# 611_jetbot_129.net
KiCad netlist of a schematic drawn in EAGLE
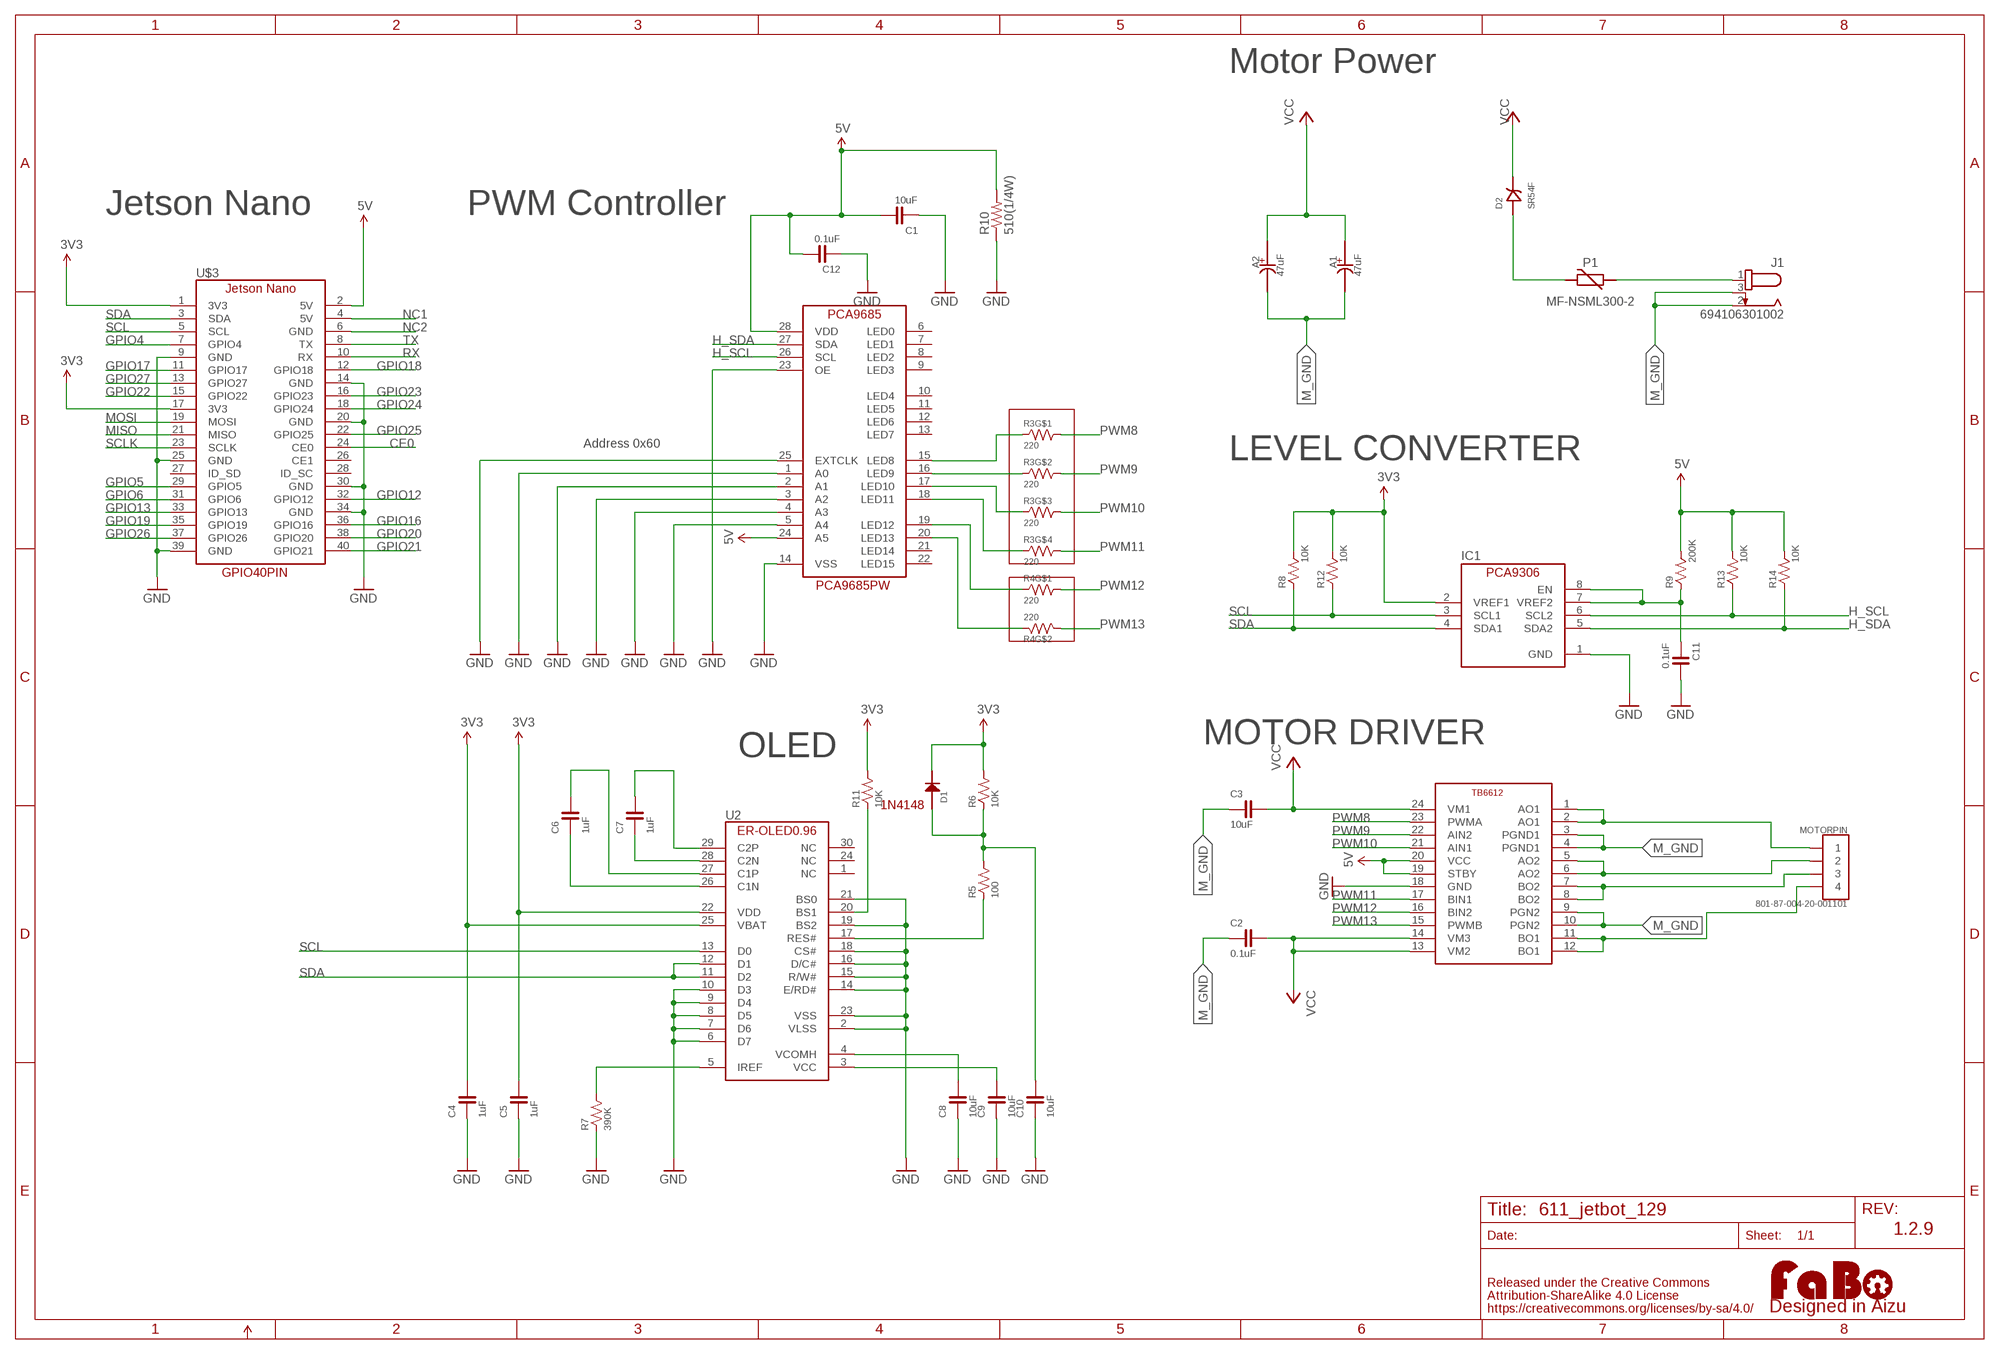
[diagram p0: schematic, sheet 1]

(export (version "E")
  (design (tool "Eeschema 10.0.6"))
  (components
    (comp (ref "A1")
      (value "47uF")
      (footprint "eagle-import:D60")
      (libsource (lib "eagle-import") (part "CAPACITOR-ALUMIN_D60"))
    )
    (comp (ref "A2")
      (value "47uF")
      (footprint "eagle-import:D60")
      (libsource (lib "eagle-import") (part "CAPACITOR-ALUMIN_D60"))
    )
    (comp (ref "C1")
      (value "10uF")
      (footprint "eagle-import:0603")
      (libsource (lib "eagle-import") (part "CAPACITOR-0603"))
    )
    (comp (ref "C2")
      (value "0.1uF")
      (footprint "eagle-import:0603")
      (libsource (lib "eagle-import") (part "CAPACITOR-0603"))
    )
    (comp (ref "C3")
      (value "10uF")
      (footprint "eagle-import:0603")
      (libsource (lib "eagle-import") (part "CAPACITOR-0603"))
    )
    (comp (ref "C4")
      (value "1uF")
      (footprint "eagle-import:0603-BOTTOM")
      (libsource (lib "eagle-import") (part "CAPACITOR-0603-BOTTOM"))
    )
    (comp (ref "C5")
      (value "1uF")
      (footprint "eagle-import:0603-BOTTOM")
      (libsource (lib "eagle-import") (part "CAPACITOR-0603-BOTTOM"))
    )
    (comp (ref "C6")
      (value "1uF")
      (footprint "eagle-import:0603-BOTTOM")
      (libsource (lib "eagle-import") (part "CAPACITOR-0603-BOTTOM"))
    )
    (comp (ref "C7")
      (value "1uF")
      (footprint "eagle-import:0603-BOTTOM")
      (libsource (lib "eagle-import") (part "CAPACITOR-0603-BOTTOM"))
    )
    (comp (ref "C8")
      (value "10uF")
      (footprint "eagle-import:0603-BOTTOM")
      (libsource (lib "eagle-import") (part "CAPACITOR-0603-BOTTOM"))
    )
    (comp (ref "C9")
      (value "10uF")
      (footprint "eagle-import:0603-BOTTOM")
      (libsource (lib "eagle-import") (part "CAPACITOR-0603-BOTTOM"))
    )
    (comp (ref "C10")
      (value "10uF")
      (footprint "eagle-import:0603-BOTTOM")
      (libsource (lib "eagle-import") (part "CAPACITOR-0603-BOTTOM"))
    )
    (comp (ref "C11")
      (value "0.1uF")
      (footprint "eagle-import:0603")
      (libsource (lib "eagle-import") (part "CAPACITOR-0603"))
    )
    (comp (ref "C12")
      (value "0.1uF")
      (footprint "eagle-import:0603")
      (libsource (lib "eagle-import") (part "CAPACITOR-0603"))
    )
    (comp (ref "D1")
      (value "1N4148")
      (footprint "eagle-import:1N4148W")
      (libsource (lib "eagle-import") (part "1N4148"))
    )
    (comp (ref "D2")
      (value "SR54F")
      (footprint "eagle-import:SMBF")
      (libsource (lib "eagle-import") (part "SR54F"))
    )
    (comp (ref "IC1")
      (value "PCA9306_SSOP")
      (footprint "eagle-import:8PIN-SSOP")
      (libsource (lib "eagle-import") (part "PCA9306_SSOP"))
    )
    (comp (ref "IC4")
      (value "PCA9685")
      (footprint "eagle-import:PCA9685")
      (libsource (lib "eagle-import") (part "PCA9685"))
    )
    (comp (ref "J1")
      (value "694106301002")
      (footprint "eagle-import:694106301002")
      (fields
        (field (name "DIGIKEY_PART_NUMBER") "732-5930-ND")
        (field (name "MANUFACTURER") "Wurth Electronics Inc.")
        (field (name "CREATED_BY") "PCBLayout.com")
      )
      (libsource (lib "eagle-import") (part "694106301002"))
    )
    (comp (ref "LOGO1")
      (value "LOGO_FABO-M")
      (footprint "eagle-import:LOGO_FABO_M")
      (libsource (lib "eagle-import") (part "LOGO_FABO-M"))
    )
    (comp (ref "MOTORPIN")
      (value "801-87-004-20-001101")
      (footprint "eagle-import:801-87-004-20-002101")
      (libsource (lib "eagle-import") (part "801-87-004-20-001101"))
    )
    (comp (ref "P1")
      (value "MF-NSML300-2")
      (footprint "eagle-import:1206")
      (libsource (lib "eagle-import") (part "POLYSWITCH1206"))
    )
    (comp (ref "R3")
      (value "220")
      (footprint "eagle-import:EXBV8V")
      (libsource (lib "eagle-import") (part "RESISTOR_ARRAY"))
    )
    (comp (ref "R4")
      (value "220")
      (footprint "eagle-import:EXBV8V")
      (libsource (lib "eagle-import") (part "RESISTOR_ARRAY"))
    )
    (comp (ref "R5")
      (value "100")
      (footprint "eagle-import:0603-BOTTOM")
      (libsource (lib "eagle-import") (part "RESISTOR-0603-BOTTOM"))
    )
    (comp (ref "R6")
      (value "10K")
      (footprint "eagle-import:0603-BOTTOM")
      (libsource (lib "eagle-import") (part "RESISTOR-0603-BOTTOM"))
    )
    (comp (ref "R7")
      (value "390K")
      (footprint "eagle-import:0603-BOTTOM")
      (libsource (lib "eagle-import") (part "RESISTOR-0603-BOTTOM"))
    )
    (comp (ref "R8")
      (value "10K")
      (footprint "eagle-import:0603")
      (libsource (lib "eagle-import") (part "RESISTOR-0603"))
    )
    (comp (ref "R9")
      (value "200K")
      (footprint "eagle-import:0603")
      (libsource (lib "eagle-import") (part "RESISTOR-0603"))
    )
    (comp (ref "R10")
      (value "510(1/4W)")
      (footprint "eagle-import:R0805")
      (libsource (lib "eagle-import") (part "R-US_R0805"))
    )
    (comp (ref "R11")
      (value "10K")
      (footprint "eagle-import:0603-BOTTOM")
      (libsource (lib "eagle-import") (part "RESISTOR-0603-BOTTOM"))
    )
    (comp (ref "R12")
      (value "10K")
      (footprint "eagle-import:0603")
      (libsource (lib "eagle-import") (part "RESISTOR-0603"))
    )
    (comp (ref "R13")
      (value "10K")
      (footprint "eagle-import:0603")
      (libsource (lib "eagle-import") (part "RESISTOR-0603"))
    )
    (comp (ref "R14")
      (value "10K")
      (footprint "eagle-import:0603")
      (libsource (lib "eagle-import") (part "RESISTOR-0603"))
    )
    (comp (ref "U$3")
      (value "JETSON_NANO")
      (footprint "eagle-import:JETSON_NANO")
      (libsource (lib "eagle-import") (part "JETSON_NANO"))
    )
    (comp (ref "U$5")
      (value "TB6612")
      (footprint "eagle-import:TB6612")
      (libsource (lib "eagle-import") (part "TB6612"))
    )
    (comp (ref "U2")
      (value "ER-OLED0.96-1ER-CON30HT-1_REV2")
      (footprint "eagle-import:ER-CON30HT-1_REV2")
      (libsource (lib "eagle-import") (part "ER-OLED0.96-1ER-CON30HT-1_REV2"))
    )
  )
  (nets
    (net (code "1") (name "/CE0") (class "Default")
      (node (ref "U$3") (pin "24") (pinfunction "CE0_24") (pintype "bidirectional"))
    )
    (net (code "2") (name "/GPIO4") (class "Default")
      (node (ref "U$3") (pin "7") (pinfunction "GPIO4_7") (pintype "bidirectional"))
    )
    (net (code "3") (name "/GPIO5") (class "Default")
      (node (ref "U$3") (pin "29") (pinfunction "GPIO5_29") (pintype "bidirectional"))
    )
    (net (code "4") (name "/GPIO6") (class "Default")
      (node (ref "U$3") (pin "31") (pinfunction "GPIO6_31") (pintype "bidirectional"))
    )
    (net (code "5") (name "/GPIO12") (class "Default")
      (node (ref "U$3") (pin "32") (pinfunction "GPIO12_32") (pintype "bidirectional"))
    )
    (net (code "6") (name "/GPIO13") (class "Default")
      (node (ref "U$3") (pin "33") (pinfunction "GPIO13_33") (pintype "bidirectional"))
    )
    (net (code "7") (name "/GPIO16") (class "Default")
      (node (ref "U$3") (pin "36") (pinfunction "GPIO16_36") (pintype "bidirectional"))
    )
    (net (code "8") (name "/GPIO17") (class "Default")
      (node (ref "U$3") (pin "11") (pinfunction "GPIO17_11") (pintype "bidirectional"))
    )
    (net (code "9") (name "/GPIO18") (class "Default")
      (node (ref "U$3") (pin "12") (pinfunction "GPIO18_12") (pintype "bidirectional"))
    )
    (net (code "10") (name "/GPIO19") (class "Default")
      (node (ref "U$3") (pin "35") (pinfunction "GPIO19_35") (pintype "bidirectional"))
    )
    (net (code "11") (name "/GPIO20") (class "Default")
      (node (ref "U$3") (pin "38") (pinfunction "GPIO20_38") (pintype "bidirectional"))
    )
    (net (code "12") (name "/GPIO21") (class "Default")
      (node (ref "U$3") (pin "40") (pinfunction "GPIO21_40") (pintype "bidirectional"))
    )
    (net (code "13") (name "/GPIO22") (class "Default")
      (node (ref "U$3") (pin "15") (pinfunction "GPIO22_15") (pintype "bidirectional"))
    )
    (net (code "14") (name "/GPIO23") (class "Default")
      (node (ref "U$3") (pin "16") (pinfunction "GPIO23_16") (pintype "bidirectional"))
    )
    (net (code "15") (name "/GPIO24") (class "Default")
      (node (ref "U$3") (pin "18") (pinfunction "GPIO24_18") (pintype "bidirectional"))
    )
    (net (code "16") (name "/GPIO25") (class "Default")
      (node (ref "U$3") (pin "22") (pinfunction "GPIO25_22") (pintype "bidirectional"))
    )
    (net (code "17") (name "/GPIO26") (class "Default")
      (node (ref "U$3") (pin "37") (pinfunction "GPIO26_37") (pintype "bidirectional"))
    )
    (net (code "18") (name "/GPIO27") (class "Default")
      (node (ref "U$3") (pin "13") (pinfunction "GPIO27_13") (pintype "bidirectional"))
    )
    (net (code "19") (name "/H_SCL") (class "Default")
      (node (ref "IC1") (pin "6") (pinfunction "SCL2_6") (pintype "bidirectional"))
      (node (ref "IC4") (pin "26") (pinfunction "SCL_26") (pintype "bidirectional"))
      (node (ref "R13") (pin "1") (pinfunction "1_1") (pintype "bidirectional"))
    )
    (net (code "20") (name "/H_SDA") (class "Default")
      (node (ref "IC1") (pin "5") (pinfunction "SDA2_5") (pintype "bidirectional"))
      (node (ref "IC4") (pin "27") (pinfunction "SDA_27") (pintype "bidirectional"))
      (node (ref "R14") (pin "1") (pinfunction "1_1") (pintype "bidirectional"))
    )
    (net (code "21") (name "/MISO") (class "Default")
      (node (ref "U$3") (pin "21") (pinfunction "MISO_21") (pintype "bidirectional"))
    )
    (net (code "22") (name "/MOSI") (class "Default")
      (node (ref "U$3") (pin "19") (pinfunction "MOSI_19") (pintype "bidirectional"))
    )
    (net (code "23") (name "/NC1") (class "Default")
      (node (ref "U$3") (pin "4") (pinfunction "5V_4") (pintype "bidirectional"))
    )
    (net (code "24") (name "/NC2") (class "Default")
      (node (ref "U$3") (pin "6") (pinfunction "GND_6") (pintype "bidirectional"))
    )
    (net (code "25") (name "/PWM8") (class "Default")
      (node (ref "R3") (pin "8") (pinfunction "2_8") (pintype "bidirectional"))
      (node (ref "U$5") (pin "23") (pinfunction "PWMA_23") (pintype "bidirectional"))
    )
    (net (code "26") (name "/PWM9") (class "Default")
      (node (ref "R3") (pin "7") (pinfunction "2_7") (pintype "bidirectional"))
      (node (ref "U$5") (pin "22") (pinfunction "AIN2_22") (pintype "bidirectional"))
    )
    (net (code "27") (name "/PWM10") (class "Default")
      (node (ref "R3") (pin "6") (pinfunction "2_6") (pintype "bidirectional"))
      (node (ref "U$5") (pin "21") (pinfunction "AIN1_21") (pintype "bidirectional"))
    )
    (net (code "28") (name "/PWM11") (class "Default")
      (node (ref "R3") (pin "5") (pinfunction "2_5") (pintype "bidirectional"))
      (node (ref "U$5") (pin "17") (pinfunction "BIN1_17") (pintype "bidirectional"))
    )
    (net (code "29") (name "/PWM12") (class "Default")
      (node (ref "R4") (pin "8") (pinfunction "2_8") (pintype "bidirectional"))
      (node (ref "U$5") (pin "16") (pinfunction "BIN2_16") (pintype "bidirectional"))
    )
    (net (code "30") (name "/PWM13") (class "Default")
      (node (ref "R4") (pin "7") (pinfunction "2_7") (pintype "bidirectional"))
      (node (ref "U$5") (pin "15") (pinfunction "PWMB_15") (pintype "bidirectional"))
    )
    (net (code "31") (name "/RX") (class "Default")
      (node (ref "U$3") (pin "10") (pinfunction "RX_10") (pintype "bidirectional"))
    )
    (net (code "32") (name "/SCL") (class "Default")
      (node (ref "IC1") (pin "3") (pinfunction "SCL1_3") (pintype "bidirectional"))
      (node (ref "R12") (pin "1") (pinfunction "1_1") (pintype "bidirectional"))
      (node (ref "U$3") (pin "5") (pinfunction "SCL_5") (pintype "bidirectional"))
      (node (ref "U2") (pin "13") (pinfunction "D0_13") (pintype "bidirectional"))
    )
    (net (code "33") (name "/SCLK") (class "Default")
      (node (ref "U$3") (pin "23") (pinfunction "SCLK_23") (pintype "bidirectional"))
    )
    (net (code "34") (name "/SDA") (class "Default")
      (node (ref "IC1") (pin "4") (pinfunction "SDA1_4") (pintype "bidirectional"))
      (node (ref "R8") (pin "1") (pinfunction "1_1") (pintype "bidirectional"))
      (node (ref "U$3") (pin "3") (pinfunction "SDA_3") (pintype "bidirectional"))
      (node (ref "U2") (pin "11") (pinfunction "D2_11") (pintype "bidirectional"))
      (node (ref "U2") (pin "12") (pinfunction "D1_12") (pintype "bidirectional"))
    )
    (net (code "35") (name "/TX") (class "Default")
      (node (ref "U$3") (pin "8") (pinfunction "TX_8") (pintype "bidirectional"))
    )
    (net (code "36") (name "3V3") (class "Default")
      (node (ref "C4") (pin "2") (pinfunction "2_2") (pintype "passive"))
      (node (ref "C5") (pin "2") (pinfunction "2_2") (pintype "passive"))
      (node (ref "D1") (pin "CATHODE") (pinfunction "CATHODE_CATHODE") (pintype "bidirectional"))
      (node (ref "IC1") (pin "2") (pinfunction "VREF1_2") (pintype "bidirectional"))
      (node (ref "R11") (pin "2") (pinfunction "2_2") (pintype "bidirectional"))
      (node (ref "R12") (pin "2") (pinfunction "2_2") (pintype "bidirectional"))
      (node (ref "R6") (pin "2") (pinfunction "2_2") (pintype "bidirectional"))
      (node (ref "R8") (pin "2") (pinfunction "2_2") (pintype "bidirectional"))
      (node (ref "U$3") (pin "1") (pinfunction "3V3_1") (pintype "bidirectional"))
      (node (ref "U$3") (pin "17") (pinfunction "3V3_17") (pintype "bidirectional"))
      (node (ref "U2") (pin "22") (pinfunction "VDD_22") (pintype "bidirectional"))
      (node (ref "U2") (pin "25") (pinfunction "VBAT_25") (pintype "bidirectional"))
    )
    (net (code "37") (name "5V") (class "Default")
      (node (ref "C1") (pin "2") (pinfunction "2_2") (pintype "passive"))
      (node (ref "C12") (pin "2") (pinfunction "2_2") (pintype "passive"))
      (node (ref "IC4") (pin "24") (pinfunction "A5_24") (pintype "bidirectional"))
      (node (ref "IC4") (pin "28") (pinfunction "VDD_28") (pintype "bidirectional"))
      (node (ref "R10") (pin "2") (pinfunction "2_2") (pintype "passive"))
      (node (ref "R13") (pin "2") (pinfunction "2_2") (pintype "bidirectional"))
      (node (ref "R14") (pin "2") (pinfunction "2_2") (pintype "bidirectional"))
      (node (ref "R9") (pin "2") (pinfunction "2_2") (pintype "bidirectional"))
      (node (ref "U$3") (pin "2") (pinfunction "5V_2") (pintype "bidirectional"))
      (node (ref "U$5") (pin "19") (pinfunction "STBY_19") (pintype "bidirectional"))
      (node (ref "U$5") (pin "20") (pinfunction "VCC_20") (pintype "bidirectional"))
    )
    (net (code "38") (name "GND") (class "Default")
      (node (ref "C1") (pin "1") (pinfunction "1_1") (pintype "passive"))
      (node (ref "C10") (pin "1") (pinfunction "1_1") (pintype "passive"))
      (node (ref "C11") (pin "2") (pinfunction "2_2") (pintype "passive"))
      (node (ref "C12") (pin "1") (pinfunction "1_1") (pintype "passive"))
      (node (ref "C4") (pin "1") (pinfunction "1_1") (pintype "passive"))
      (node (ref "C5") (pin "1") (pinfunction "1_1") (pintype "passive"))
      (node (ref "C8") (pin "1") (pinfunction "1_1") (pintype "passive"))
      (node (ref "C9") (pin "1") (pinfunction "1_1") (pintype "passive"))
      (node (ref "IC1") (pin "1") (pinfunction "GND_1") (pintype "bidirectional"))
      (node (ref "IC4") (pin "1") (pinfunction "A0_1") (pintype "bidirectional"))
      (node (ref "IC4") (pin "14") (pinfunction "VSS_14") (pintype "bidirectional"))
      (node (ref "IC4") (pin "2") (pinfunction "A1_2") (pintype "bidirectional"))
      (node (ref "IC4") (pin "23") (pinfunction "OE_23") (pintype "bidirectional"))
      (node (ref "IC4") (pin "25") (pinfunction "EXTCLK_25") (pintype "bidirectional"))
      (node (ref "IC4") (pin "3") (pinfunction "A2_3") (pintype "bidirectional"))
      (node (ref "IC4") (pin "4") (pinfunction "A3_4") (pintype "bidirectional"))
      (node (ref "IC4") (pin "5") (pinfunction "A4_5") (pintype "bidirectional"))
      (node (ref "R10") (pin "1") (pinfunction "1_1") (pintype "passive"))
      (node (ref "R7") (pin "1") (pinfunction "1_1") (pintype "bidirectional"))
      (node (ref "U$3") (pin "14") (pinfunction "GND_14") (pintype "bidirectional"))
      (node (ref "U$3") (pin "20") (pinfunction "GND_20") (pintype "bidirectional"))
      (node (ref "U$3") (pin "25") (pinfunction "GND_25") (pintype "bidirectional"))
      (node (ref "U$3") (pin "30") (pinfunction "GND_30") (pintype "bidirectional"))
      (node (ref "U$3") (pin "34") (pinfunction "GND_34") (pintype "bidirectional"))
      (node (ref "U$3") (pin "39") (pinfunction "GND_39") (pintype "bidirectional"))
      (node (ref "U$3") (pin "9") (pinfunction "GND_9") (pintype "bidirectional"))
      (node (ref "U$5") (pin "18") (pinfunction "GND_18") (pintype "bidirectional"))
      (node (ref "U2") (pin "10") (pinfunction "D3_10") (pintype "bidirectional"))
      (node (ref "U2") (pin "14") (pinfunction "E/RD#_14") (pintype "bidirectional"))
      (node (ref "U2") (pin "15") (pinfunction "R/W#_15") (pintype "bidirectional"))
      (node (ref "U2") (pin "16") (pinfunction "D/C#_16") (pintype "bidirectional"))
      (node (ref "U2") (pin "18") (pinfunction "CS#_18") (pintype "bidirectional"))
      (node (ref "U2") (pin "19") (pinfunction "BS2_19") (pintype "bidirectional"))
      (node (ref "U2") (pin "2") (pinfunction "VLSS_2") (pintype "bidirectional"))
      (node (ref "U2") (pin "21") (pinfunction "BS0_21") (pintype "bidirectional"))
      (node (ref "U2") (pin "23") (pinfunction "VSS_23") (pintype "bidirectional"))
      (node (ref "U2") (pin "6") (pinfunction "D7_6") (pintype "bidirectional"))
      (node (ref "U2") (pin "7") (pinfunction "D6_7") (pintype "bidirectional"))
      (node (ref "U2") (pin "8") (pinfunction "D5_8") (pintype "bidirectional"))
      (node (ref "U2") (pin "9") (pinfunction "D4_9") (pintype "bidirectional"))
    )
    (net (code "39") (name "M_GND") (class "Default")
      (node (ref "A1") (pin "MINUS") (pinfunction "-_MINUS") (pintype "passive"))
      (node (ref "A2") (pin "MINUS") (pinfunction "-_MINUS") (pintype "passive"))
      (node (ref "C2") (pin "1") (pinfunction "1_1") (pintype "passive"))
      (node (ref "C3") (pin "1") (pinfunction "1_1") (pintype "passive"))
      (node (ref "J1") (pin "2") (pinfunction "2_2") (pintype "passive"))
      (node (ref "J1") (pin "3") (pinfunction "3_3") (pintype "passive"))
      (node (ref "U$5") (pin "10") (pinfunction "PGN2_10") (pintype "bidirectional"))
      (node (ref "U$5") (pin "3") (pinfunction "PGND1_3") (pintype "bidirectional"))
      (node (ref "U$5") (pin "4") (pinfunction "PGND1_4") (pintype "bidirectional"))
      (node (ref "U$5") (pin "9") (pinfunction "PGN2_9") (pintype "bidirectional"))
    )
    (net (code "40") (name "Net-(C10-Pad2)") (class "Default")
      (node (ref "C10") (pin "2") (pinfunction "2_2") (pintype "passive"))
      (node (ref "D1") (pin "ANODE") (pinfunction "ANODE_ANODE") (pintype "bidirectional"))
      (node (ref "R5") (pin "2") (pinfunction "2_2") (pintype "bidirectional"))
      (node (ref "R6") (pin "1") (pinfunction "1_1") (pintype "bidirectional"))
    )
    (net (code "41") (name "Net-(D2-PadANODE)") (class "Default")
      (node (ref "D2") (pin "ANODE") (pinfunction "ANODE_ANODE") (pintype "bidirectional"))
      (node (ref "P1") (pin "2") (pinfunction "2_2") (pintype "bidirectional"))
    )
    (net (code "42") (name "Net-(IC1-EN)") (class "Default")
      (node (ref "C11") (pin "1") (pinfunction "1_1") (pintype "passive"))
      (node (ref "IC1") (pin "7") (pinfunction "VREF2_7") (pintype "bidirectional"))
      (node (ref "IC1") (pin "8") (pinfunction "EN_8") (pintype "bidirectional"))
      (node (ref "R9") (pin "1") (pinfunction "1_1") (pintype "bidirectional"))
    )
    (net (code "43") (name "Net-(IC4-LED8)") (class "Default")
      (node (ref "IC4") (pin "15") (pinfunction "LED8_15") (pintype "bidirectional"))
      (node (ref "R3") (pin "1") (pinfunction "1_1") (pintype "bidirectional"))
    )
    (net (code "44") (name "Net-(IC4-LED9)") (class "Default")
      (node (ref "IC4") (pin "16") (pinfunction "LED9_16") (pintype "bidirectional"))
      (node (ref "R3") (pin "2") (pinfunction "1_2") (pintype "bidirectional"))
    )
    (net (code "45") (name "Net-(IC4-LED10)") (class "Default")
      (node (ref "IC4") (pin "17") (pinfunction "LED10_17") (pintype "bidirectional"))
      (node (ref "R3") (pin "3") (pinfunction "1_3") (pintype "bidirectional"))
    )
    (net (code "46") (name "Net-(IC4-LED11)") (class "Default")
      (node (ref "IC4") (pin "18") (pinfunction "LED11_18") (pintype "bidirectional"))
      (node (ref "R3") (pin "4") (pinfunction "1_4") (pintype "bidirectional"))
    )
    (net (code "47") (name "Net-(IC4-LED12)") (class "Default")
      (node (ref "IC4") (pin "19") (pinfunction "LED12_19") (pintype "bidirectional"))
      (node (ref "R4") (pin "1") (pinfunction "1_1") (pintype "bidirectional"))
    )
    (net (code "48") (name "Net-(IC4-LED13)") (class "Default")
      (node (ref "IC4") (pin "20") (pinfunction "LED13_20") (pintype "bidirectional"))
      (node (ref "R4") (pin "2") (pinfunction "1_2") (pintype "bidirectional"))
    )
    (net (code "49") (name "Net-(J1-Pad1)") (class "Default")
      (node (ref "J1") (pin "1") (pinfunction "1_1") (pintype "passive"))
      (node (ref "P1") (pin "1") (pinfunction "1_1") (pintype "bidirectional"))
    )
    (net (code "50") (name "Net-(MOTORPIN-Pad1)") (class "Default")
      (node (ref "MOTORPIN") (pin "1") (pinfunction "1_1") (pintype "bidirectional"))
      (node (ref "U$5") (pin "1") (pinfunction "AO1_1") (pintype "bidirectional"))
      (node (ref "U$5") (pin "2") (pinfunction "AO1_2") (pintype "bidirectional"))
    )
    (net (code "51") (name "Net-(MOTORPIN-Pad2)") (class "Default")
      (node (ref "MOTORPIN") (pin "2") (pinfunction "2_2") (pintype "bidirectional"))
      (node (ref "U$5") (pin "5") (pinfunction "AO2_5") (pintype "bidirectional"))
      (node (ref "U$5") (pin "6") (pinfunction "AO2_6") (pintype "bidirectional"))
    )
    (net (code "52") (name "Net-(MOTORPIN-Pad3)") (class "Default")
      (node (ref "MOTORPIN") (pin "3") (pinfunction "3_3") (pintype "bidirectional"))
      (node (ref "U$5") (pin "7") (pinfunction "BO2_7") (pintype "bidirectional"))
      (node (ref "U$5") (pin "8") (pinfunction "BO2_8") (pintype "bidirectional"))
    )
    (net (code "53") (name "Net-(MOTORPIN-Pad4)") (class "Default")
      (node (ref "MOTORPIN") (pin "4") (pinfunction "4_4") (pintype "bidirectional"))
      (node (ref "U$5") (pin "11") (pinfunction "BO1_11") (pintype "bidirectional"))
      (node (ref "U$5") (pin "12") (pinfunction "BO1_12") (pintype "bidirectional"))
    )
    (net (code "54") (name "Net-(U2-BS1)") (class "Default")
      (node (ref "R11") (pin "1") (pinfunction "1_1") (pintype "bidirectional"))
      (node (ref "U2") (pin "20") (pinfunction "BS1_20") (pintype "bidirectional"))
    )
    (net (code "55") (name "Net-(U2-C1N)") (class "Default")
      (node (ref "C6") (pin "1") (pinfunction "1_1") (pintype "passive"))
      (node (ref "U2") (pin "26") (pinfunction "C1N_26") (pintype "bidirectional"))
    )
    (net (code "56") (name "Net-(U2-C1P)") (class "Default")
      (node (ref "C6") (pin "2") (pinfunction "2_2") (pintype "passive"))
      (node (ref "U2") (pin "27") (pinfunction "C1P_27") (pintype "bidirectional"))
    )
    (net (code "57") (name "Net-(U2-C2N)") (class "Default")
      (node (ref "C7") (pin "1") (pinfunction "1_1") (pintype "passive"))
      (node (ref "U2") (pin "28") (pinfunction "C2N_28") (pintype "bidirectional"))
    )
    (net (code "58") (name "Net-(U2-C2P)") (class "Default")
      (node (ref "C7") (pin "2") (pinfunction "2_2") (pintype "passive"))
      (node (ref "U2") (pin "29") (pinfunction "C2P_29") (pintype "bidirectional"))
    )
    (net (code "59") (name "Net-(U2-IREF)") (class "Default")
      (node (ref "R7") (pin "2") (pinfunction "2_2") (pintype "bidirectional"))
      (node (ref "U2") (pin "5") (pinfunction "IREF_5") (pintype "bidirectional"))
    )
    (net (code "60") (name "Net-(U2-RES#)") (class "Default")
      (node (ref "R5") (pin "1") (pinfunction "1_1") (pintype "bidirectional"))
      (node (ref "U2") (pin "17") (pinfunction "RES#_17") (pintype "bidirectional"))
    )
    (net (code "61") (name "Net-(U2-VCC)") (class "Default")
      (node (ref "C9") (pin "2") (pinfunction "2_2") (pintype "passive"))
      (node (ref "U2") (pin "3") (pinfunction "VCC_3") (pintype "bidirectional"))
    )
    (net (code "62") (name "Net-(U2-VCOMH)") (class "Default")
      (node (ref "C8") (pin "2") (pinfunction "2_2") (pintype "passive"))
      (node (ref "U2") (pin "4") (pinfunction "VCOMH_4") (pintype "bidirectional"))
    )
    (net (code "63") (name "VCC") (class "Default")
      (node (ref "A1") (pin "PLUS") (pinfunction "+_PLUS") (pintype "passive"))
      (node (ref "A2") (pin "PLUS") (pinfunction "+_PLUS") (pintype "passive"))
      (node (ref "C2") (pin "2") (pinfunction "2_2") (pintype "passive"))
      (node (ref "C3") (pin "2") (pinfunction "2_2") (pintype "passive"))
      (node (ref "D2") (pin "CATHODE") (pinfunction "CATHODE_CATHODE") (pintype "bidirectional"))
      (node (ref "U$5") (pin "13") (pinfunction "VM2_13") (pintype "bidirectional"))
      (node (ref "U$5") (pin "14") (pinfunction "VM3_14") (pintype "bidirectional"))
      (node (ref "U$5") (pin "24") (pinfunction "VM1_24") (pintype "bidirectional"))
    )
    (net (code "64") (name "unconnected-(IC4-LED0-Pad6)") (class "Default")
      (node (ref "IC4") (pin "6") (pinfunction "LED0_6") (pintype "bidirectional"))
    )
    (net (code "65") (name "unconnected-(IC4-LED1-Pad7)") (class "Default")
      (node (ref "IC4") (pin "7") (pinfunction "LED1_7") (pintype "bidirectional"))
    )
    (net (code "66") (name "unconnected-(IC4-LED2-Pad8)") (class "Default")
      (node (ref "IC4") (pin "8") (pinfunction "LED2_8") (pintype "bidirectional"))
    )
    (net (code "67") (name "unconnected-(IC4-LED3-Pad9)") (class "Default")
      (node (ref "IC4") (pin "9") (pinfunction "LED3_9") (pintype "bidirectional"))
    )
    (net (code "68") (name "unconnected-(IC4-LED4-Pad10)") (class "Default")
      (node (ref "IC4") (pin "10") (pinfunction "LED4_10") (pintype "bidirectional"))
    )
    (net (code "69") (name "unconnected-(IC4-LED5-Pad11)") (class "Default")
      (node (ref "IC4") (pin "11") (pinfunction "LED5_11") (pintype "bidirectional"))
    )
    (net (code "70") (name "unconnected-(IC4-LED6-Pad12)") (class "Default")
      (node (ref "IC4") (pin "12") (pinfunction "LED6_12") (pintype "bidirectional"))
    )
    (net (code "71") (name "unconnected-(IC4-LED7-Pad13)") (class "Default")
      (node (ref "IC4") (pin "13") (pinfunction "LED7_13") (pintype "bidirectional"))
    )
    (net (code "72") (name "unconnected-(IC4-LED14-Pad21)") (class "Default")
      (node (ref "IC4") (pin "21") (pinfunction "LED14_21") (pintype "bidirectional"))
    )
    (net (code "73") (name "unconnected-(IC4-LED15-Pad22)") (class "Default")
      (node (ref "IC4") (pin "22") (pinfunction "LED15_22") (pintype "bidirectional"))
    )
    (net (code "74") (name "unconnected-(U$3-CE1-Pad26)") (class "Default")
      (node (ref "U$3") (pin "26") (pinfunction "CE1_26") (pintype "bidirectional"))
    )
    (net (code "75") (name "unconnected-(U$3-ID_SC-Pad28)") (class "Default")
      (node (ref "U$3") (pin "28") (pinfunction "ID_SC_28") (pintype "bidirectional"))
    )
    (net (code "76") (name "unconnected-(U$3-ID_SD-Pad27)") (class "Default")
      (node (ref "U$3") (pin "27") (pinfunction "ID_SD_27") (pintype "bidirectional"))
    )
    (net (code "77") (name "unconnected-(U2-NC-Pad1)") (class "Default")
      (node (ref "U2") (pin "1") (pinfunction "NC_1") (pintype "bidirectional"))
    )
    (net (code "78") (name "unconnected-(U2-NC-Pad24)") (class "Default")
      (node (ref "U2") (pin "24") (pinfunction "NC_24") (pintype "bidirectional"))
    )
    (net (code "79") (name "unconnected-(U2-NC-Pad30)") (class "Default")
      (node (ref "U2") (pin "30") (pinfunction "NC_30") (pintype "bidirectional"))
    )
  )
)
